# GTIA2DVI.net
KiCad netlist of a schematic drawn in EAGLE
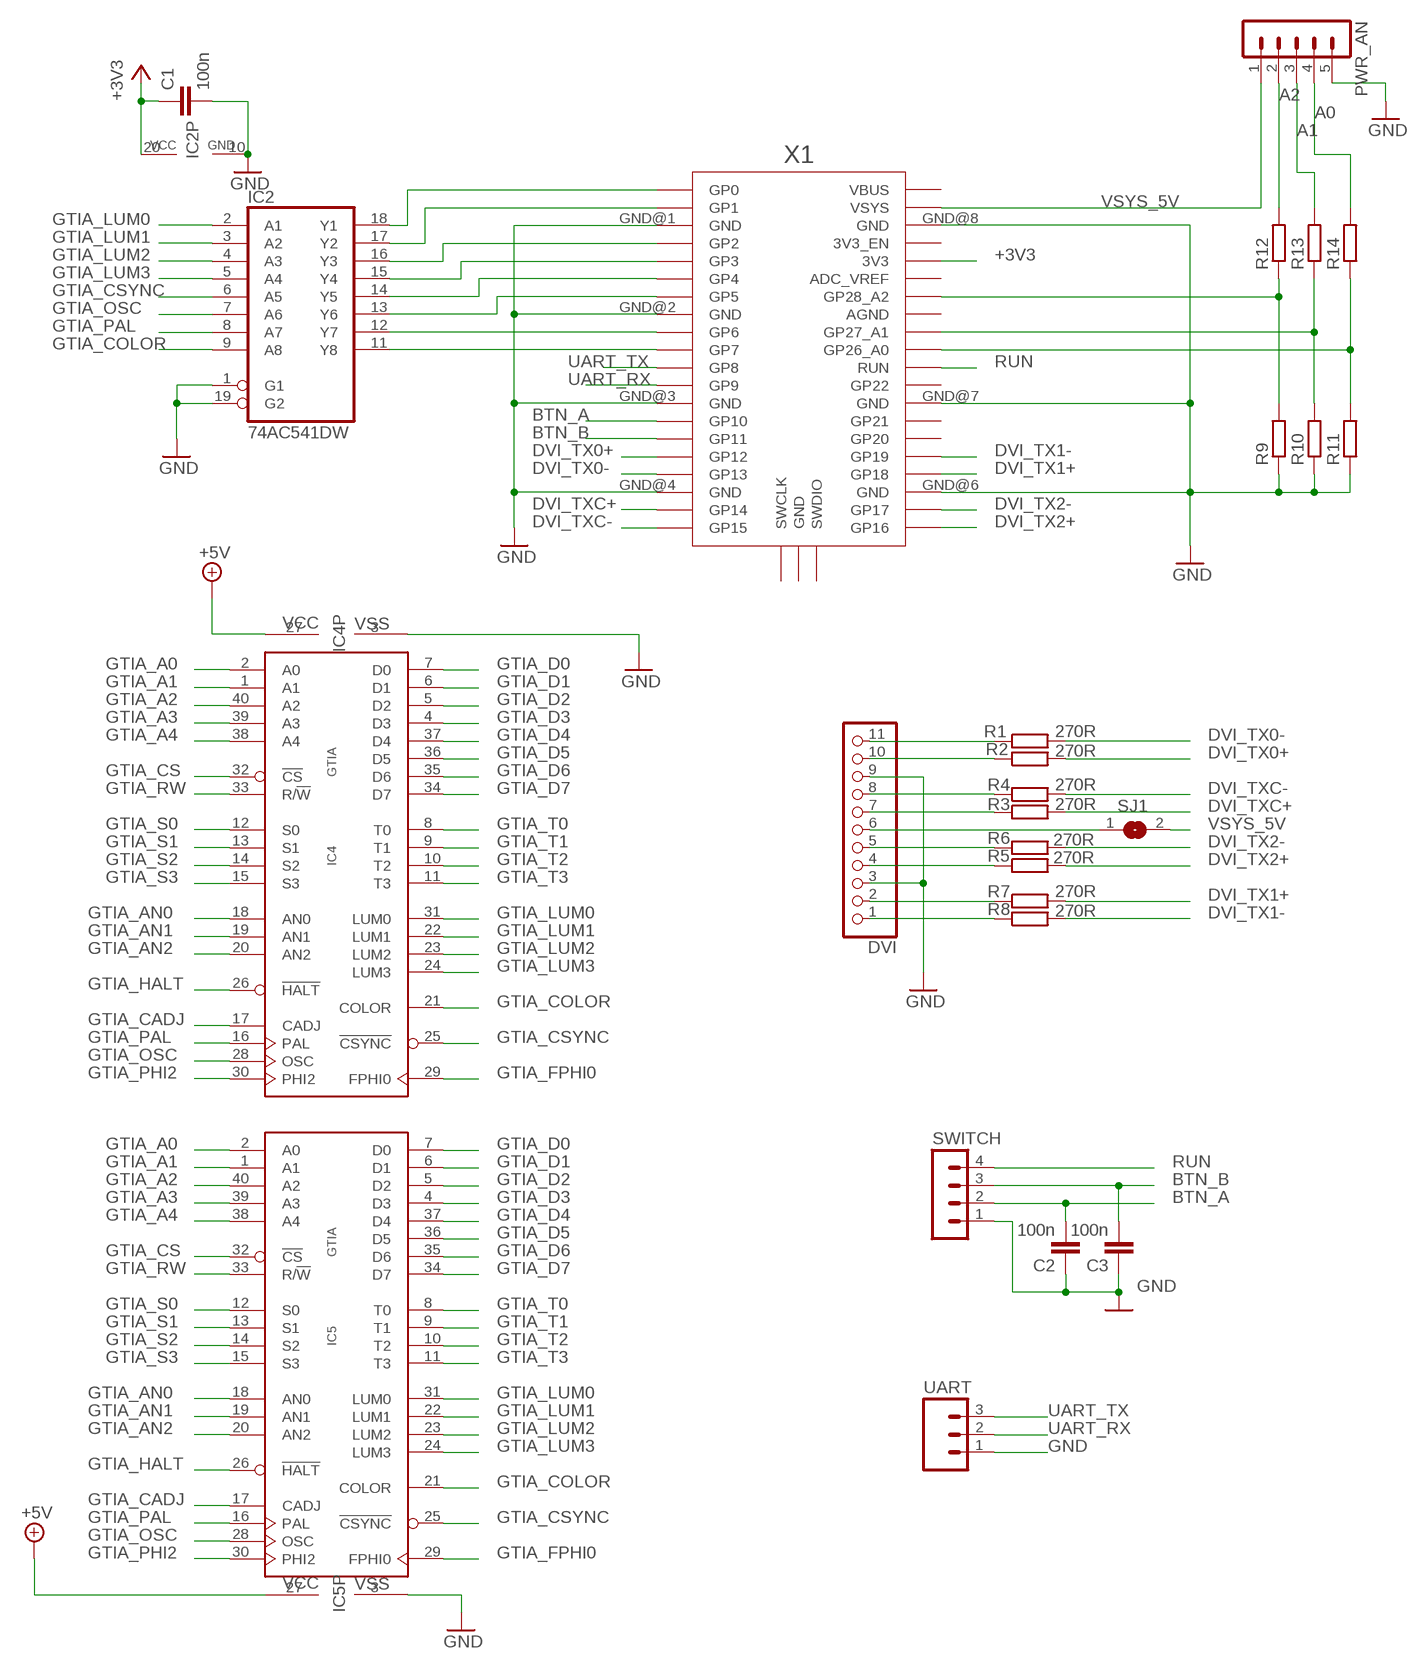
[diagram p0: schematic, sheet 1]

(export (version "E")
  (design (tool "Eeschema 10.0.6"))
  (components
    (comp (ref "C1")
      (value "100n")
      (footprint "eagle-import:C0805")
      (libsource (lib "eagle-import") (part "C-EUC0805"))
    )
    (comp (ref "C2")
      (value "100n")
      (footprint "eagle-import:C0805")
      (libsource (lib "eagle-import") (part "C-EUC0805"))
    )
    (comp (ref "C3")
      (value "100n")
      (footprint "eagle-import:C0805")
      (libsource (lib "eagle-import") (part "C-EUC0805"))
    )
    (comp (ref "DVI")
      (value "PINHD-1X11")
      (footprint "eagle-import:1X11")
      (libsource (lib "eagle-import") (part "PINHD-1X11"))
    )
    (comp (ref "IC2")
      (value "74AC541DW")
      (footprint "eagle-import:SO20W")
      (libsource (lib "eagle-import") (part "74541DWAC"))
    )
    (comp (ref "IC4")
      (value "GTIA")
      (footprint "eagle-import:DIL40")
      (libsource (lib "eagle-import") (part "GTIA"))
    )
    (comp (ref "IC5")
      (value "GTIA")
      (footprint "eagle-import:DIL40")
      (libsource (lib "eagle-import") (part "GTIA"))
    )
    (comp (ref "PWR_AN")
      (value "MA05-1")
      (footprint "eagle-import:MA05-1")
      (libsource (lib "eagle-import") (part "MA05-1"))
    )
    (comp (ref "R1")
      (value "270R")
      (footprint "eagle-import:M0805")
      (libsource (lib "eagle-import") (part "R-EU_M0805"))
    )
    (comp (ref "R2")
      (value "270R")
      (footprint "eagle-import:M0805")
      (libsource (lib "eagle-import") (part "R-EU_M0805"))
    )
    (comp (ref "R3")
      (value "270R")
      (footprint "eagle-import:M0805")
      (libsource (lib "eagle-import") (part "R-EU_M0805"))
    )
    (comp (ref "R4")
      (value "270R")
      (footprint "eagle-import:M0805")
      (libsource (lib "eagle-import") (part "R-EU_M0805"))
    )
    (comp (ref "R5")
      (value "270R")
      (footprint "eagle-import:M0805")
      (libsource (lib "eagle-import") (part "R-EU_M0805"))
    )
    (comp (ref "R6")
      (value "270R")
      (footprint "eagle-import:M0805")
      (libsource (lib "eagle-import") (part "R-EU_M0805"))
    )
    (comp (ref "R7")
      (value "270R")
      (footprint "eagle-import:M0805")
      (libsource (lib "eagle-import") (part "R-EU_M0805"))
    )
    (comp (ref "R8")
      (value "270R")
      (footprint "eagle-import:M0805")
      (libsource (lib "eagle-import") (part "R-EU_M0805"))
    )
    (comp (ref "R9")
      (value "R-EU_M0805")
      (footprint "eagle-import:M0805")
      (libsource (lib "eagle-import") (part "R-EU_M0805"))
    )
    (comp (ref "R10")
      (value "R-EU_M0805")
      (footprint "eagle-import:M0805")
      (libsource (lib "eagle-import") (part "R-EU_M0805"))
    )
    (comp (ref "R11")
      (value "R-EU_M0805")
      (footprint "eagle-import:M0805")
      (libsource (lib "eagle-import") (part "R-EU_M0805"))
    )
    (comp (ref "R12")
      (value "R-EU_M0805")
      (footprint "eagle-import:M0805")
      (libsource (lib "eagle-import") (part "R-EU_M0805"))
    )
    (comp (ref "R13")
      (value "R-EU_M0805")
      (footprint "eagle-import:M0805")
      (libsource (lib "eagle-import") (part "R-EU_M0805"))
    )
    (comp (ref "R14")
      (value "R-EU_M0805")
      (footprint "eagle-import:M0805")
      (libsource (lib "eagle-import") (part "R-EU_M0805"))
    )
    (comp (ref "SJ1") (value "SJ") (footprint "eagle-import:SJ") (libsource (lib "eagle-import") (part "SJ")))
    (comp (ref "SWITCH")
      (value "MA04-1")
      (footprint "eagle-import:MA04-1")
      (libsource (lib "eagle-import") (part "MA04-1"))
    )
    (comp (ref "UART")
      (value "MA03")
      (footprint "eagle-import:03P")
      (libsource (lib "eagle-import") (part "MA03"))
    )
    (comp (ref "X1")
      (value "RPI_PICO_IG-TH")
      (footprint "eagle-import:RPI_PICO_TH")
      (libsource (lib "eagle-import") (part "RPI_PICO_IG-TH"))
    )
  )
  (nets
    (net (code "1") (name "+3V3") (class "Default")
      (node (ref "C1") (pin "1") (pinfunction "1_1") (pintype "passive"))
      (node (ref "IC2") (pin "20") (pinfunction "VCC_20") (pintype "power_in"))
      (node (ref "X1") (pin "3V3") (pinfunction "3V3_3V3") (pintype "bidirectional"))
    )
    (net (code "2") (name "+5V") (class "Default")
      (node (ref "IC4") (pin "27") (pinfunction "VCC_27") (pintype "power_in"))
      (node (ref "IC5") (pin "27") (pinfunction "VCC_27") (pintype "power_in"))
    )
    (net (code "3") (name "/A0") (class "Default")
      (node (ref "PWR_AN") (pin "4") (pinfunction "4_4") (pintype "passive"))
      (node (ref "R14") (pin "2") (pinfunction "2_2") (pintype "passive"))
    )
    (net (code "4") (name "/A1") (class "Default")
      (node (ref "PWR_AN") (pin "3") (pinfunction "3_3") (pintype "passive"))
      (node (ref "R13") (pin "2") (pinfunction "2_2") (pintype "passive"))
    )
    (net (code "5") (name "/A2") (class "Default")
      (node (ref "PWR_AN") (pin "2") (pinfunction "2_2") (pintype "passive"))
      (node (ref "R12") (pin "2") (pinfunction "2_2") (pintype "passive"))
    )
    (net (code "6") (name "/BTN_A") (class "Default")
      (node (ref "C2") (pin "2") (pinfunction "2_2") (pintype "passive"))
      (node (ref "SWITCH") (pin "2") (pinfunction "2_2") (pintype "passive"))
      (node (ref "X1") (pin "GP10") (pinfunction "GP10_GP10") (pintype "bidirectional"))
    )
    (net (code "7") (name "/BTN_B") (class "Default")
      (node (ref "C3") (pin "2") (pinfunction "2_2") (pintype "passive"))
      (node (ref "SWITCH") (pin "3") (pinfunction "3_3") (pintype "passive"))
      (node (ref "X1") (pin "GP11") (pinfunction "GP11_GP11") (pintype "bidirectional"))
    )
    (net (code "8") (name "/DVI_TX0+") (class "Default")
      (node (ref "R2") (pin "2") (pinfunction "2_2") (pintype "passive"))
      (node (ref "X1") (pin "GP12") (pinfunction "GP12_GP12") (pintype "bidirectional"))
    )
    (net (code "9") (name "/DVI_TX0-") (class "Default")
      (node (ref "R1") (pin "2") (pinfunction "2_2") (pintype "passive"))
      (node (ref "X1") (pin "GP13") (pinfunction "GP13_GP13") (pintype "bidirectional"))
    )
    (net (code "10") (name "/DVI_TX1+") (class "Default")
      (node (ref "R7") (pin "2") (pinfunction "2_2") (pintype "passive"))
      (node (ref "X1") (pin "GP18") (pinfunction "GP18_GP18") (pintype "bidirectional"))
    )
    (net (code "11") (name "/DVI_TX1-") (class "Default")
      (node (ref "R8") (pin "2") (pinfunction "2_2") (pintype "passive"))
      (node (ref "X1") (pin "GP19") (pinfunction "GP19_GP19") (pintype "bidirectional"))
    )
    (net (code "12") (name "/DVI_TX2+") (class "Default")
      (node (ref "R5") (pin "2") (pinfunction "2_2") (pintype "passive"))
      (node (ref "X1") (pin "GP16") (pinfunction "GP16_GP16") (pintype "bidirectional"))
    )
    (net (code "13") (name "/DVI_TX2-") (class "Default")
      (node (ref "R6") (pin "2") (pinfunction "2_2") (pintype "passive"))
      (node (ref "X1") (pin "GP17") (pinfunction "GP17_GP17") (pintype "bidirectional"))
    )
    (net (code "14") (name "/DVI_TXC+") (class "Default")
      (node (ref "R3") (pin "2") (pinfunction "2_2") (pintype "passive"))
      (node (ref "X1") (pin "GP14") (pinfunction "GP14_GP14") (pintype "bidirectional"))
    )
    (net (code "15") (name "/DVI_TXC-") (class "Default")
      (node (ref "R4") (pin "2") (pinfunction "2_2") (pintype "passive"))
      (node (ref "X1") (pin "GP15") (pinfunction "GP15_GP15") (pintype "bidirectional"))
    )
    (net (code "16") (name "/GTIA_A0") (class "Default")
      (node (ref "IC4") (pin "2") (pinfunction "A0_2") (pintype "input"))
      (node (ref "IC5") (pin "2") (pinfunction "A0_2") (pintype "input"))
    )
    (net (code "17") (name "/GTIA_A1") (class "Default")
      (node (ref "IC4") (pin "1") (pinfunction "A1_1") (pintype "input"))
      (node (ref "IC5") (pin "1") (pinfunction "A1_1") (pintype "input"))
    )
    (net (code "18") (name "/GTIA_A2") (class "Default")
      (node (ref "IC4") (pin "40") (pinfunction "A2_40") (pintype "input"))
      (node (ref "IC5") (pin "40") (pinfunction "A2_40") (pintype "input"))
    )
    (net (code "19") (name "/GTIA_A3") (class "Default")
      (node (ref "IC4") (pin "39") (pinfunction "A3_39") (pintype "input"))
      (node (ref "IC5") (pin "39") (pinfunction "A3_39") (pintype "input"))
    )
    (net (code "20") (name "/GTIA_A4") (class "Default")
      (node (ref "IC4") (pin "38") (pinfunction "A4_38") (pintype "input"))
      (node (ref "IC5") (pin "38") (pinfunction "A4_38") (pintype "input"))
    )
    (net (code "21") (name "/GTIA_AN0") (class "Default")
      (node (ref "IC4") (pin "18") (pinfunction "AN0_18") (pintype "input"))
      (node (ref "IC5") (pin "18") (pinfunction "AN0_18") (pintype "input"))
    )
    (net (code "22") (name "/GTIA_AN1") (class "Default")
      (node (ref "IC4") (pin "19") (pinfunction "AN1_19") (pintype "input"))
      (node (ref "IC5") (pin "19") (pinfunction "AN1_19") (pintype "input"))
    )
    (net (code "23") (name "/GTIA_AN2") (class "Default")
      (node (ref "IC4") (pin "20") (pinfunction "AN2_20") (pintype "input"))
      (node (ref "IC5") (pin "20") (pinfunction "AN2_20") (pintype "input"))
    )
    (net (code "24") (name "/GTIA_CADJ") (class "Default")
      (node (ref "IC4") (pin "17") (pinfunction "CADJ_17") (pintype "input"))
      (node (ref "IC5") (pin "17") (pinfunction "CADJ_17") (pintype "input"))
    )
    (net (code "25") (name "/GTIA_COLOR") (class "Default")
      (node (ref "IC2") (pin "9") (pinfunction "A8_9") (pintype "input"))
      (node (ref "IC4") (pin "21") (pinfunction "COLOR_21") (pintype "output"))
      (node (ref "IC5") (pin "21") (pinfunction "COLOR_21") (pintype "output"))
    )
    (net (code "26") (name "/GTIA_CS") (class "Default")
      (node (ref "IC4") (pin "32") (pinfunction "~{CS}_32") (pintype "input"))
      (node (ref "IC5") (pin "32") (pinfunction "~{CS}_32") (pintype "input"))
    )
    (net (code "27") (name "/GTIA_CSYNC") (class "Default")
      (node (ref "IC2") (pin "6") (pinfunction "A5_6") (pintype "input"))
      (node (ref "IC4") (pin "25") (pinfunction "~{CSYNC}_25") (pintype "output"))
      (node (ref "IC5") (pin "25") (pinfunction "~{CSYNC}_25") (pintype "output"))
    )
    (net (code "28") (name "/GTIA_D0") (class "Default")
      (node (ref "IC4") (pin "7") (pinfunction "D0_7") (pintype "output"))
      (node (ref "IC5") (pin "7") (pinfunction "D0_7") (pintype "output"))
    )
    (net (code "29") (name "/GTIA_D1") (class "Default")
      (node (ref "IC4") (pin "6") (pinfunction "D1_6") (pintype "output"))
      (node (ref "IC5") (pin "6") (pinfunction "D1_6") (pintype "output"))
    )
    (net (code "30") (name "/GTIA_D2") (class "Default")
      (node (ref "IC4") (pin "5") (pinfunction "D2_5") (pintype "output"))
      (node (ref "IC5") (pin "5") (pinfunction "D2_5") (pintype "output"))
    )
    (net (code "31") (name "/GTIA_D3") (class "Default")
      (node (ref "IC4") (pin "4") (pinfunction "D3_4") (pintype "output"))
      (node (ref "IC5") (pin "4") (pinfunction "D3_4") (pintype "output"))
    )
    (net (code "32") (name "/GTIA_D4") (class "Default")
      (node (ref "IC4") (pin "37") (pinfunction "D4_37") (pintype "output"))
      (node (ref "IC5") (pin "37") (pinfunction "D4_37") (pintype "output"))
    )
    (net (code "33") (name "/GTIA_D5") (class "Default")
      (node (ref "IC4") (pin "36") (pinfunction "D5_36") (pintype "output"))
      (node (ref "IC5") (pin "36") (pinfunction "D5_36") (pintype "output"))
    )
    (net (code "34") (name "/GTIA_D6") (class "Default")
      (node (ref "IC4") (pin "35") (pinfunction "D6_35") (pintype "output"))
      (node (ref "IC5") (pin "35") (pinfunction "D6_35") (pintype "output"))
    )
    (net (code "35") (name "/GTIA_D7") (class "Default")
      (node (ref "IC4") (pin "34") (pinfunction "D7_34") (pintype "output"))
      (node (ref "IC5") (pin "34") (pinfunction "D7_34") (pintype "output"))
    )
    (net (code "36") (name "/GTIA_FPHI0") (class "Default")
      (node (ref "IC4") (pin "29") (pinfunction "FPHI0_29") (pintype "output"))
      (node (ref "IC5") (pin "29") (pinfunction "FPHI0_29") (pintype "output"))
    )
    (net (code "37") (name "/GTIA_HALT") (class "Default")
      (node (ref "IC4") (pin "26") (pinfunction "~{HALT}_26") (pintype "input"))
      (node (ref "IC5") (pin "26") (pinfunction "~{HALT}_26") (pintype "input"))
    )
    (net (code "38") (name "/GTIA_LUM0") (class "Default")
      (node (ref "IC2") (pin "2") (pinfunction "A1_2") (pintype "input"))
      (node (ref "IC4") (pin "31") (pinfunction "LUM0_31") (pintype "output"))
      (node (ref "IC5") (pin "31") (pinfunction "LUM0_31") (pintype "output"))
    )
    (net (code "39") (name "/GTIA_LUM1") (class "Default")
      (node (ref "IC2") (pin "3") (pinfunction "A2_3") (pintype "input"))
      (node (ref "IC4") (pin "22") (pinfunction "LUM1_22") (pintype "output"))
      (node (ref "IC5") (pin "22") (pinfunction "LUM1_22") (pintype "output"))
    )
    (net (code "40") (name "/GTIA_LUM2") (class "Default")
      (node (ref "IC2") (pin "4") (pinfunction "A3_4") (pintype "input"))
      (node (ref "IC4") (pin "23") (pinfunction "LUM2_23") (pintype "output"))
      (node (ref "IC5") (pin "23") (pinfunction "LUM2_23") (pintype "output"))
    )
    (net (code "41") (name "/GTIA_LUM3") (class "Default")
      (node (ref "IC2") (pin "5") (pinfunction "A4_5") (pintype "input"))
      (node (ref "IC4") (pin "24") (pinfunction "LUM3_24") (pintype "output"))
      (node (ref "IC5") (pin "24") (pinfunction "LUM3_24") (pintype "output"))
    )
    (net (code "42") (name "/GTIA_OSC") (class "Default")
      (node (ref "IC2") (pin "7") (pinfunction "A6_7") (pintype "input"))
      (node (ref "IC4") (pin "28") (pinfunction "OSC_28") (pintype "input"))
      (node (ref "IC5") (pin "28") (pinfunction "OSC_28") (pintype "input"))
    )
    (net (code "43") (name "/GTIA_PAL") (class "Default")
      (node (ref "IC2") (pin "8") (pinfunction "A7_8") (pintype "input"))
      (node (ref "IC4") (pin "16") (pinfunction "PAL_16") (pintype "input"))
      (node (ref "IC5") (pin "16") (pinfunction "PAL_16") (pintype "input"))
    )
    (net (code "44") (name "/GTIA_PHI2") (class "Default")
      (node (ref "IC4") (pin "30") (pinfunction "PHI2_30") (pintype "input"))
      (node (ref "IC5") (pin "30") (pinfunction "PHI2_30") (pintype "input"))
    )
    (net (code "45") (name "/GTIA_RW") (class "Default")
      (node (ref "IC4") (pin "33") (pinfunction "R/~{W}_33") (pintype "input"))
      (node (ref "IC5") (pin "33") (pinfunction "R/~{W}_33") (pintype "input"))
    )
    (net (code "46") (name "/GTIA_S0") (class "Default")
      (node (ref "IC4") (pin "12") (pinfunction "S0_12") (pintype "bidirectional"))
      (node (ref "IC5") (pin "12") (pinfunction "S0_12") (pintype "bidirectional"))
    )
    (net (code "47") (name "/GTIA_S1") (class "Default")
      (node (ref "IC4") (pin "13") (pinfunction "S1_13") (pintype "bidirectional"))
      (node (ref "IC5") (pin "13") (pinfunction "S1_13") (pintype "bidirectional"))
    )
    (net (code "48") (name "/GTIA_S2") (class "Default")
      (node (ref "IC4") (pin "14") (pinfunction "S2_14") (pintype "output"))
      (node (ref "IC5") (pin "14") (pinfunction "S2_14") (pintype "output"))
    )
    (net (code "49") (name "/GTIA_S3") (class "Default")
      (node (ref "IC4") (pin "15") (pinfunction "S3_15") (pintype "output"))
      (node (ref "IC5") (pin "15") (pinfunction "S3_15") (pintype "output"))
    )
    (net (code "50") (name "/GTIA_T0") (class "Default")
      (node (ref "IC4") (pin "8") (pinfunction "T0_8") (pintype "input"))
      (node (ref "IC5") (pin "8") (pinfunction "T0_8") (pintype "input"))
    )
    (net (code "51") (name "/GTIA_T1") (class "Default")
      (node (ref "IC4") (pin "9") (pinfunction "T1_9") (pintype "input"))
      (node (ref "IC5") (pin "9") (pinfunction "T1_9") (pintype "input"))
    )
    (net (code "52") (name "/GTIA_T2") (class "Default")
      (node (ref "IC4") (pin "10") (pinfunction "T2_10") (pintype "input"))
      (node (ref "IC5") (pin "10") (pinfunction "T2_10") (pintype "input"))
    )
    (net (code "53") (name "/GTIA_T3") (class "Default")
      (node (ref "IC4") (pin "11") (pinfunction "T3_11") (pintype "input"))
      (node (ref "IC5") (pin "11") (pinfunction "T3_11") (pintype "input"))
    )
    (net (code "54") (name "/RUN") (class "Default")
      (node (ref "SWITCH") (pin "4") (pinfunction "4_4") (pintype "passive"))
      (node (ref "X1") (pin "RUN") (pinfunction "RUN_RUN") (pintype "bidirectional"))
    )
    (net (code "55") (name "/UART_RX") (class "Default")
      (node (ref "UART") (pin "2") (pinfunction "2_2") (pintype "passive"))
      (node (ref "X1") (pin "GP9") (pinfunction "GP9_GP9") (pintype "bidirectional"))
    )
    (net (code "56") (name "/UART_TX") (class "Default")
      (node (ref "UART") (pin "3") (pinfunction "3_3") (pintype "passive"))
      (node (ref "X1") (pin "GP8") (pinfunction "GP8_GP8") (pintype "bidirectional"))
    )
    (net (code "57") (name "/VSYS_5V") (class "Default")
      (node (ref "DVI") (pin "6") (pinfunction "6_6") (pintype "passive"))
      (node (ref "PWR_AN") (pin "1") (pinfunction "1_1") (pintype "passive"))
      (node (ref "SJ1") (pin "1") (pinfunction "1_1") (pintype "passive"))
      (node (ref "SJ1") (pin "2") (pinfunction "2_2") (pintype "passive"))
      (node (ref "X1") (pin "VSYS") (pinfunction "VSYS_VSYS") (pintype "bidirectional"))
    )
    (net (code "58") (name "GND") (class "Default")
      (node (ref "C1") (pin "2") (pinfunction "2_2") (pintype "passive"))
      (node (ref "C2") (pin "1") (pinfunction "1_1") (pintype "passive"))
      (node (ref "C3") (pin "1") (pinfunction "1_1") (pintype "passive"))
      (node (ref "DVI") (pin "3") (pinfunction "3_3") (pintype "passive"))
      (node (ref "DVI") (pin "9") (pinfunction "9_9") (pintype "passive"))
      (node (ref "IC2") (pin "1") (pinfunction "G1_1") (pintype "input"))
      (node (ref "IC2") (pin "10") (pinfunction "GND_10") (pintype "power_in"))
      (node (ref "IC2") (pin "19") (pinfunction "G2_19") (pintype "input"))
      (node (ref "IC4") (pin "3") (pinfunction "VSS_3") (pintype "power_in"))
      (node (ref "IC5") (pin "3") (pinfunction "VSS_3") (pintype "power_in"))
      (node (ref "PWR_AN") (pin "5") (pinfunction "5_5") (pintype "passive"))
      (node (ref "R10") (pin "1") (pinfunction "1_1") (pintype "passive"))
      (node (ref "R11") (pin "1") (pinfunction "1_1") (pintype "passive"))
      (node (ref "R9") (pin "1") (pinfunction "1_1") (pintype "passive"))
      (node (ref "SWITCH") (pin "1") (pinfunction "1_1") (pintype "passive"))
      (node (ref "UART") (pin "1") (pinfunction "1_1") (pintype "passive"))
      (node (ref "X1") (pin "GND@1") (pinfunction "GND_GND@1") (pintype "bidirectional"))
      (node (ref "X1") (pin "GND@2") (pinfunction "GND_GND@2") (pintype "bidirectional"))
      (node (ref "X1") (pin "GND@3") (pinfunction "GND_GND@3") (pintype "bidirectional"))
      (node (ref "X1") (pin "GND@4") (pinfunction "GND_GND@4") (pintype "bidirectional"))
      (node (ref "X1") (pin "GND@6") (pinfunction "GND_GND@6") (pintype "bidirectional"))
      (node (ref "X1") (pin "GND@7") (pinfunction "GND_GND@7") (pintype "bidirectional"))
      (node (ref "X1") (pin "GND@8") (pinfunction "GND_GND@8") (pintype "bidirectional"))
    )
    (net (code "59") (name "Net-(DVI-Pad1)") (class "Default")
      (node (ref "DVI") (pin "1") (pinfunction "1_1") (pintype "passive"))
      (node (ref "R8") (pin "1") (pinfunction "1_1") (pintype "passive"))
    )
    (net (code "60") (name "Net-(DVI-Pad2)") (class "Default")
      (node (ref "DVI") (pin "2") (pinfunction "2_2") (pintype "passive"))
      (node (ref "R7") (pin "1") (pinfunction "1_1") (pintype "passive"))
    )
    (net (code "61") (name "Net-(DVI-Pad4)") (class "Default")
      (node (ref "DVI") (pin "4") (pinfunction "4_4") (pintype "passive"))
      (node (ref "R5") (pin "1") (pinfunction "1_1") (pintype "passive"))
    )
    (net (code "62") (name "Net-(DVI-Pad5)") (class "Default")
      (node (ref "DVI") (pin "5") (pinfunction "5_5") (pintype "passive"))
      (node (ref "R6") (pin "1") (pinfunction "1_1") (pintype "passive"))
    )
    (net (code "63") (name "Net-(DVI-Pad7)") (class "Default")
      (node (ref "DVI") (pin "7") (pinfunction "7_7") (pintype "passive"))
      (node (ref "R3") (pin "1") (pinfunction "1_1") (pintype "passive"))
    )
    (net (code "64") (name "Net-(DVI-Pad8)") (class "Default")
      (node (ref "DVI") (pin "8") (pinfunction "8_8") (pintype "passive"))
      (node (ref "R4") (pin "1") (pinfunction "1_1") (pintype "passive"))
    )
    (net (code "65") (name "Net-(DVI-Pad10)") (class "Default")
      (node (ref "DVI") (pin "10") (pinfunction "10_10") (pintype "passive"))
      (node (ref "R2") (pin "1") (pinfunction "1_1") (pintype "passive"))
    )
    (net (code "66") (name "Net-(DVI-Pad11)") (class "Default")
      (node (ref "DVI") (pin "11") (pinfunction "11_11") (pintype "passive"))
      (node (ref "R1") (pin "1") (pinfunction "1_1") (pintype "passive"))
    )
    (net (code "67") (name "Net-(IC2A-Y1)") (class "Default")
      (node (ref "IC2") (pin "18") (pinfunction "Y1_18") (pintype "tri_state"))
      (node (ref "X1") (pin "GP0") (pinfunction "GP0_GP0") (pintype "bidirectional"))
    )
    (net (code "68") (name "Net-(IC2A-Y2)") (class "Default")
      (node (ref "IC2") (pin "17") (pinfunction "Y2_17") (pintype "tri_state"))
      (node (ref "X1") (pin "GP1") (pinfunction "GP1_GP1") (pintype "bidirectional"))
    )
    (net (code "69") (name "Net-(IC2A-Y3)") (class "Default")
      (node (ref "IC2") (pin "16") (pinfunction "Y3_16") (pintype "tri_state"))
      (node (ref "X1") (pin "GP2") (pinfunction "GP2_GP2") (pintype "bidirectional"))
    )
    (net (code "70") (name "Net-(IC2A-Y4)") (class "Default")
      (node (ref "IC2") (pin "15") (pinfunction "Y4_15") (pintype "tri_state"))
      (node (ref "X1") (pin "GP3") (pinfunction "GP3_GP3") (pintype "bidirectional"))
    )
    (net (code "71") (name "Net-(IC2A-Y5)") (class "Default")
      (node (ref "IC2") (pin "14") (pinfunction "Y5_14") (pintype "tri_state"))
      (node (ref "X1") (pin "GP4") (pinfunction "GP4_GP4") (pintype "bidirectional"))
    )
    (net (code "72") (name "Net-(IC2A-Y6)") (class "Default")
      (node (ref "IC2") (pin "13") (pinfunction "Y6_13") (pintype "tri_state"))
      (node (ref "X1") (pin "GP5") (pinfunction "GP5_GP5") (pintype "bidirectional"))
    )
    (net (code "73") (name "Net-(IC2A-Y7)") (class "Default")
      (node (ref "IC2") (pin "12") (pinfunction "Y7_12") (pintype "tri_state"))
      (node (ref "X1") (pin "GP6") (pinfunction "GP6_GP6") (pintype "bidirectional"))
    )
    (net (code "74") (name "Net-(IC2A-Y8)") (class "Default")
      (node (ref "IC2") (pin "11") (pinfunction "Y8_11") (pintype "tri_state"))
      (node (ref "X1") (pin "GP7") (pinfunction "GP7_GP7") (pintype "bidirectional"))
    )
    (net (code "75") (name "Net-(R10-Pad2)") (class "Default")
      (node (ref "R10") (pin "2") (pinfunction "2_2") (pintype "passive"))
      (node (ref "R13") (pin "1") (pinfunction "1_1") (pintype "passive"))
      (node (ref "X1") (pin "GP27_A1") (pinfunction "GP27_A1_GP27_A1") (pintype "bidirectional"))
    )
    (net (code "76") (name "Net-(R11-Pad2)") (class "Default")
      (node (ref "R11") (pin "2") (pinfunction "2_2") (pintype "passive"))
      (node (ref "R14") (pin "1") (pinfunction "1_1") (pintype "passive"))
      (node (ref "X1") (pin "GP26_A0") (pinfunction "GP26_A0_GP26_A0") (pintype "bidirectional"))
    )
    (net (code "77") (name "Net-(R12-Pad1)") (class "Default")
      (node (ref "R12") (pin "1") (pinfunction "1_1") (pintype "passive"))
      (node (ref "R9") (pin "2") (pinfunction "2_2") (pintype "passive"))
      (node (ref "X1") (pin "GP28_A2") (pinfunction "GP28_A2_GP28_A2") (pintype "bidirectional"))
    )
    (net (code "78") (name "unconnected-(X1-GND-PadGND@5)") (class "Default")
      (node (ref "X1") (pin "GND@5") (pinfunction "GND_GND@5") (pintype "bidirectional"))
    )
    (net (code "79") (name "unconnected-(X1-Pad3V3_EN)") (class "Default")
      (node (ref "X1") (pin "3V3_EN") (pinfunction "3V3_EN_3V3_EN") (pintype "bidirectional"))
    )
    (net (code "80") (name "unconnected-(X1-PadADC_VREF)") (class "Default")
      (node (ref "X1") (pin "ADC_VREF") (pinfunction "ADC_VREF_ADC_VREF") (pintype "bidirectional"))
    )
    (net (code "81") (name "unconnected-(X1-PadAGND)") (class "Default")
      (node (ref "X1") (pin "AGND") (pinfunction "AGND_AGND") (pintype "bidirectional"))
    )
    (net (code "82") (name "unconnected-(X1-PadGP20)") (class "Default")
      (node (ref "X1") (pin "GP20") (pinfunction "GP20_GP20") (pintype "bidirectional"))
    )
    (net (code "83") (name "unconnected-(X1-PadGP21)") (class "Default")
      (node (ref "X1") (pin "GP21") (pinfunction "GP21_GP21") (pintype "bidirectional"))
    )
    (net (code "84") (name "unconnected-(X1-PadGP22)") (class "Default")
      (node (ref "X1") (pin "GP22") (pinfunction "GP22_GP22") (pintype "bidirectional"))
    )
    (net (code "85") (name "unconnected-(X1-PadSWCLK)") (class "Default")
      (node (ref "X1") (pin "SWCLK") (pinfunction "SWCLK_SWCLK") (pintype "bidirectional"))
    )
    (net (code "86") (name "unconnected-(X1-PadSWDIO)") (class "Default")
      (node (ref "X1") (pin "SWDIO") (pinfunction "SWDIO_SWDIO") (pintype "bidirectional"))
    )
    (net (code "87") (name "unconnected-(X1-PadVBUS)") (class "Default")
      (node (ref "X1") (pin "VBUS") (pinfunction "VBUS_VBUS") (pintype "bidirectional"))
    )
  )
)
